# Adapter_board.net
KiCad netlist of a schematic drawn in EAGLE
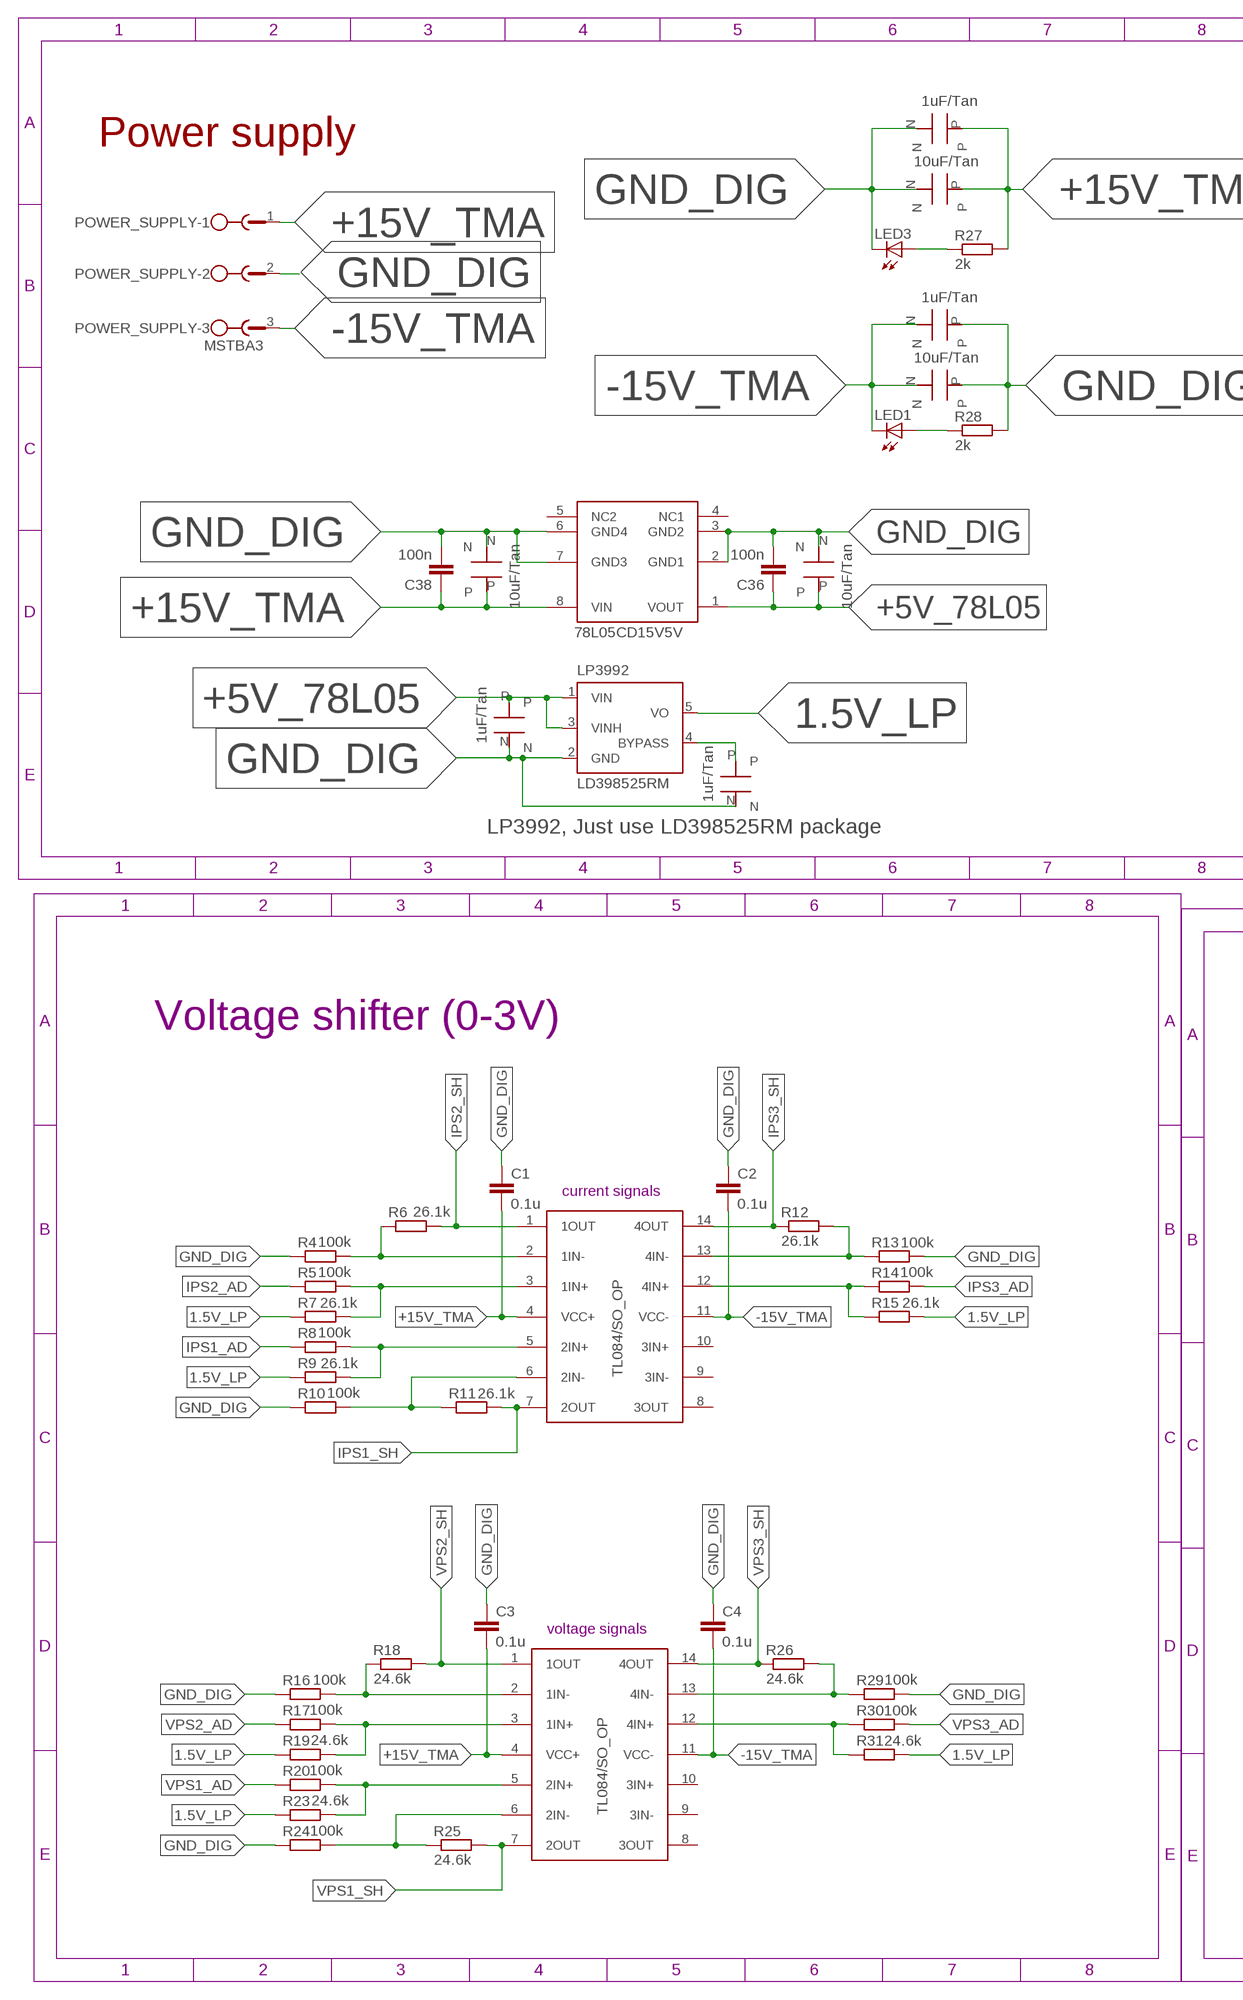
[diagram p0: schematic, sheet 1, part 1 of 2]
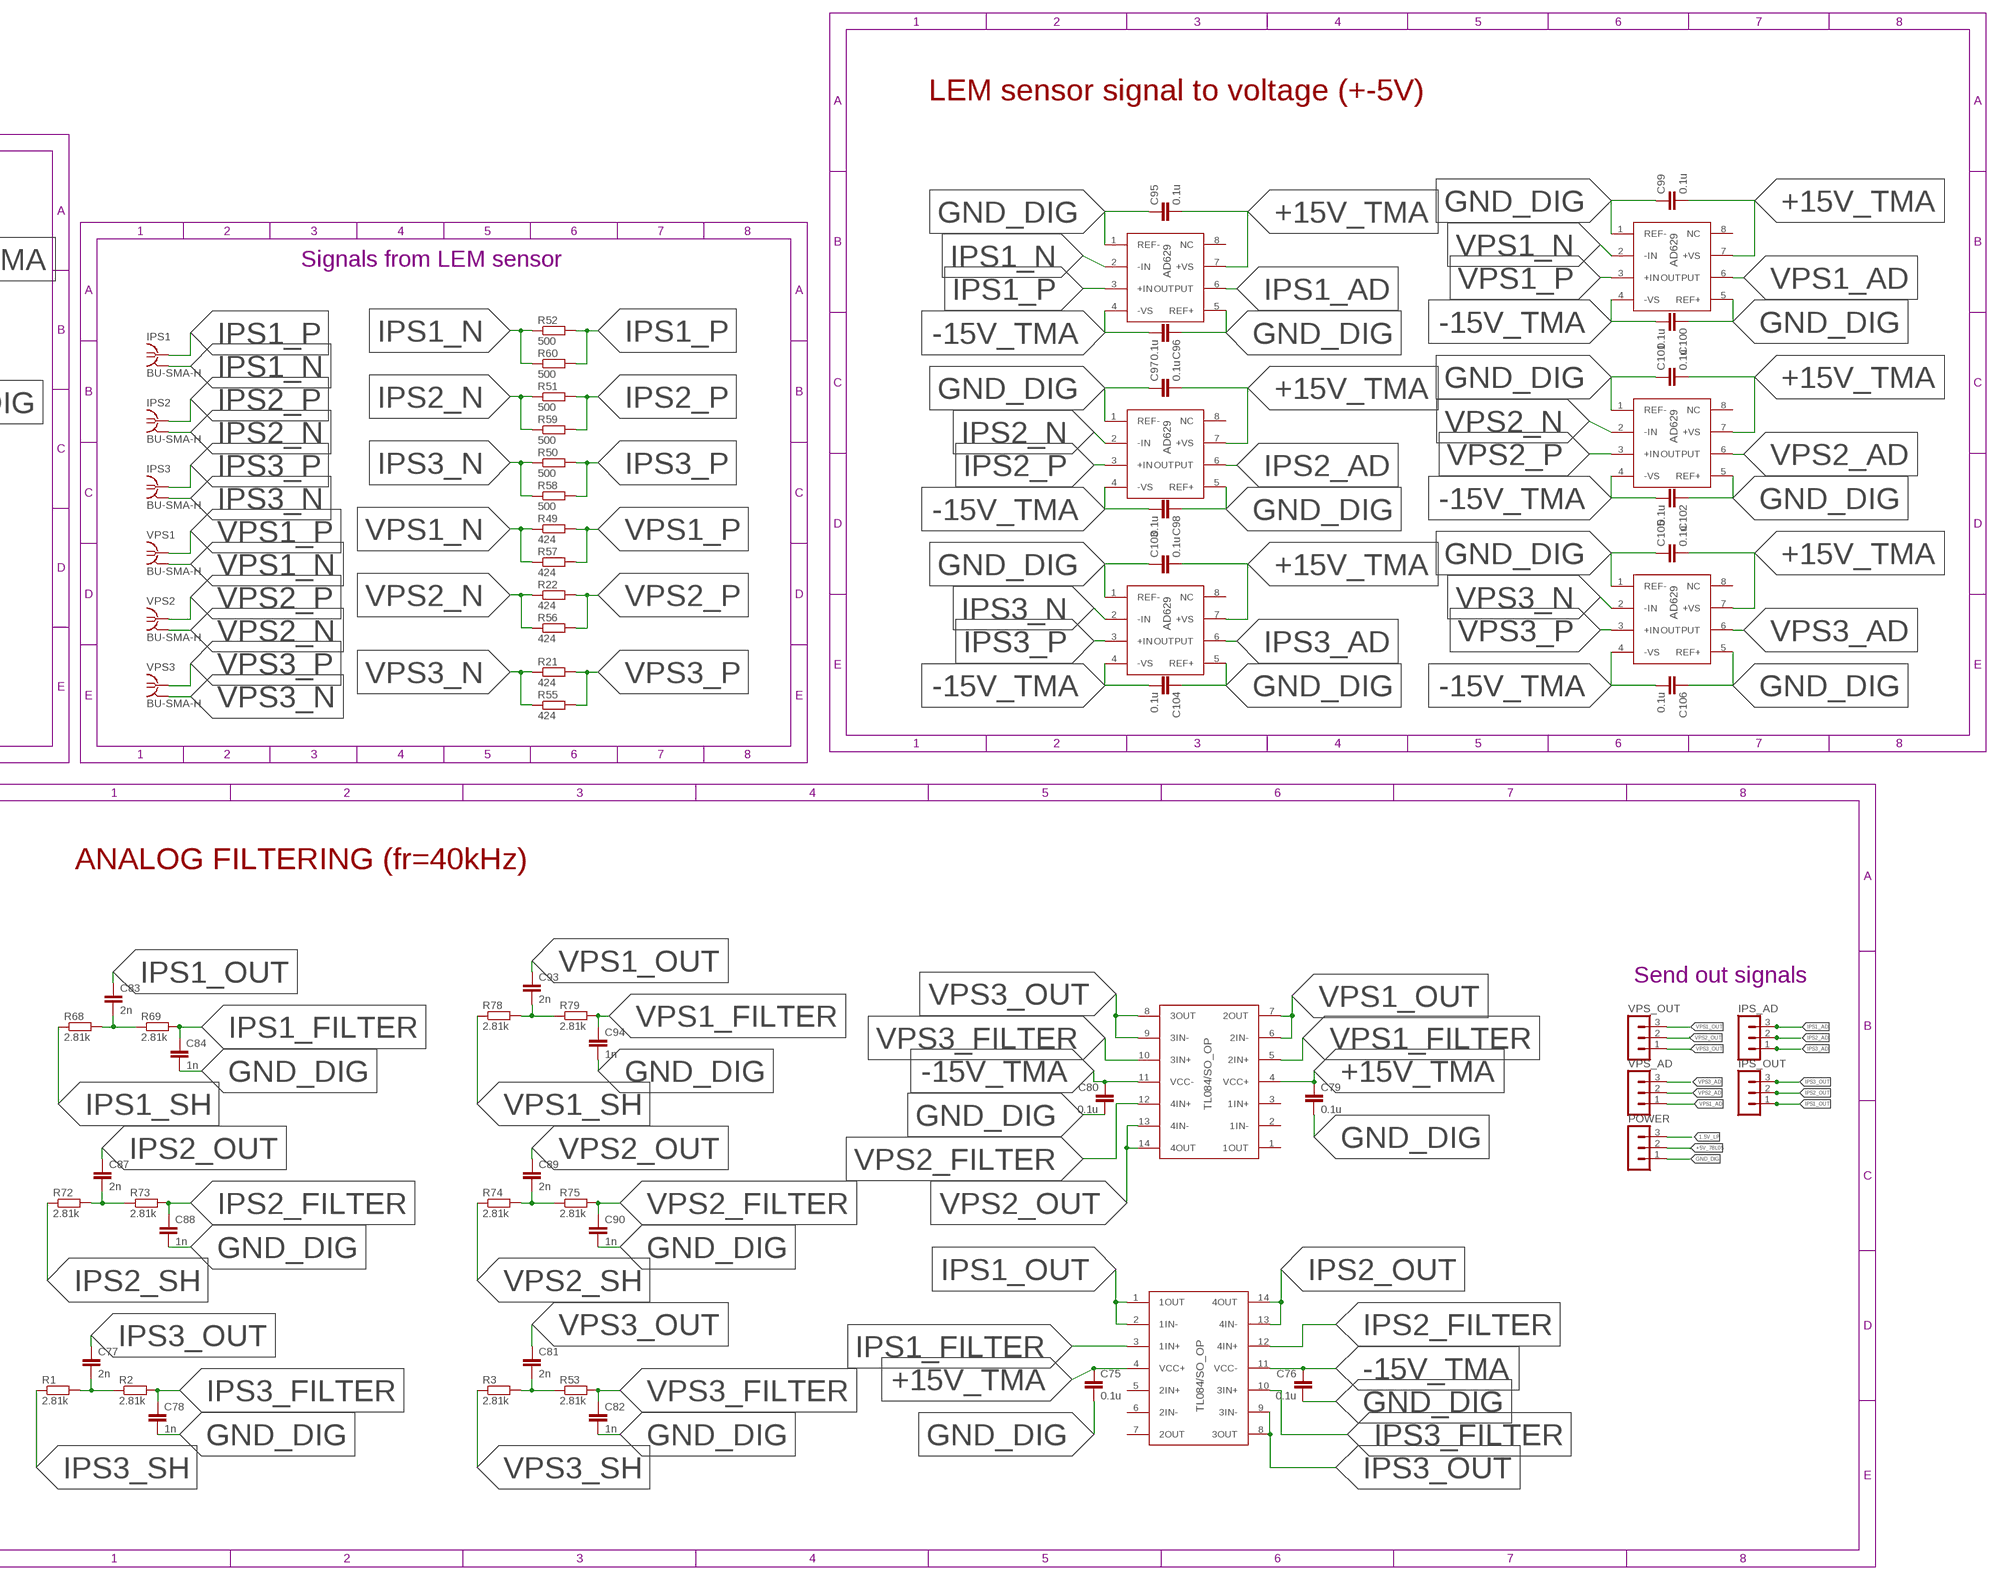
[diagram p1: schematic, sheet 1, part 2 of 2]

(export (version "E")
  (design (tool "Eeschema 10.0.6"))
  (components
    (comp (ref "78L05")
      (value "78L05CD15V5VONLINE")
      (footprint "eagle-import:78L05CD15V5V_LIB")
      (libsource (lib "eagle-import") (part "78L05CD15V5VONLINE"))
    )
    (comp (ref "C1")
      (value "0.1u")
      (footprint "eagle-import:C0805")
      (libsource (lib "eagle-import") (part "C-EUC0805"))
    )
    (comp (ref "C2")
      (value "0.1u")
      (footprint "eagle-import:C0805")
      (libsource (lib "eagle-import") (part "C-EUC0805"))
    )
    (comp (ref "C3")
      (value "0.1u")
      (footprint "eagle-import:C0805")
      (libsource (lib "eagle-import") (part "C-EUC0805"))
    )
    (comp (ref "C4")
      (value "0.1u")
      (footprint "eagle-import:C0805")
      (libsource (lib "eagle-import") (part "C-EUC0805"))
    )
    (comp (ref "C36")
      (value "100n")
      (footprint "eagle-import:C0805")
      (libsource (lib "eagle-import") (part "C-EUC0805"))
    )
    (comp (ref "C37")
      (value "TANTALUM_C_10UF_KEM")
      (footprint "eagle-import:TANTALUM_C_10UF_KEM")
      (libsource (lib "eagle-import") (part "TANTALUM_C_10UF_KEM"))
    )
    (comp (ref "C38")
      (value "100n")
      (footprint "eagle-import:C0805")
      (libsource (lib "eagle-import") (part "C-EUC0805"))
    )
    (comp (ref "C75")
      (value "0.1u")
      (footprint "eagle-import:C0805")
      (libsource (lib "eagle-import") (part "C-EUC0805"))
    )
    (comp (ref "C76")
      (value "0.1u")
      (footprint "eagle-import:C0805")
      (libsource (lib "eagle-import") (part "C-EUC0805"))
    )
    (comp (ref "C77")
      (value "2n")
      (footprint "eagle-import:C0805")
      (libsource (lib "eagle-import") (part "C-EUC0805"))
    )
    (comp (ref "C78")
      (value "1n")
      (footprint "eagle-import:C0805")
      (libsource (lib "eagle-import") (part "C-EUC0805"))
    )
    (comp (ref "C79")
      (value "0.1u")
      (footprint "eagle-import:C0805")
      (libsource (lib "eagle-import") (part "C-EUC0805"))
    )
    (comp (ref "C80")
      (value "0.1u")
      (footprint "eagle-import:C0805")
      (libsource (lib "eagle-import") (part "C-EUC0805"))
    )
    (comp (ref "C81")
      (value "2n")
      (footprint "eagle-import:C0805")
      (libsource (lib "eagle-import") (part "C-EUC0805"))
    )
    (comp (ref "C82")
      (value "1n")
      (footprint "eagle-import:C0805")
      (libsource (lib "eagle-import") (part "C-EUC0805"))
    )
    (comp (ref "C83")
      (value "2n")
      (footprint "eagle-import:C0805")
      (libsource (lib "eagle-import") (part "C-EUC0805"))
    )
    (comp (ref "C84")
      (value "1n")
      (footprint "eagle-import:C0805")
      (libsource (lib "eagle-import") (part "C-EUC0805"))
    )
    (comp (ref "C87")
      (value "2n")
      (footprint "eagle-import:C0805")
      (libsource (lib "eagle-import") (part "C-EUC0805"))
    )
    (comp (ref "C88")
      (value "1n")
      (footprint "eagle-import:C0805")
      (libsource (lib "eagle-import") (part "C-EUC0805"))
    )
    (comp (ref "C89")
      (value "2n")
      (footprint "eagle-import:C0805")
      (libsource (lib "eagle-import") (part "C-EUC0805"))
    )
    (comp (ref "C90")
      (value "1n")
      (footprint "eagle-import:C0805")
      (libsource (lib "eagle-import") (part "C-EUC0805"))
    )
    (comp (ref "C93")
      (value "2n")
      (footprint "eagle-import:C0805")
      (libsource (lib "eagle-import") (part "C-EUC0805"))
    )
    (comp (ref "C94")
      (value "1n")
      (footprint "eagle-import:C0805")
      (libsource (lib "eagle-import") (part "C-EUC0805"))
    )
    (comp (ref "C95")
      (value "0.1u")
      (footprint "eagle-import:C0805")
      (libsource (lib "eagle-import") (part "C-EUC0805"))
    )
    (comp (ref "C96")
      (value "0.1u")
      (footprint "eagle-import:C0805")
      (libsource (lib "eagle-import") (part "C-EUC0805"))
    )
    (comp (ref "C97")
      (value "0.1u")
      (footprint "eagle-import:C0805")
      (libsource (lib "eagle-import") (part "C-EUC0805"))
    )
    (comp (ref "C98")
      (value "0.1u")
      (footprint "eagle-import:C0805")
      (libsource (lib "eagle-import") (part "C-EUC0805"))
    )
    (comp (ref "C99")
      (value "0.1u")
      (footprint "eagle-import:C0805")
      (libsource (lib "eagle-import") (part "C-EUC0805"))
    )
    (comp (ref "C100")
      (value "0.1u")
      (footprint "eagle-import:C0805")
      (libsource (lib "eagle-import") (part "C-EUC0805"))
    )
    (comp (ref "C101")
      (value "0.1u")
      (footprint "eagle-import:C0805")
      (libsource (lib "eagle-import") (part "C-EUC0805"))
    )
    (comp (ref "C102")
      (value "0.1u")
      (footprint "eagle-import:C0805")
      (libsource (lib "eagle-import") (part "C-EUC0805"))
    )
    (comp (ref "C103")
      (value "0.1u")
      (footprint "eagle-import:C0805")
      (libsource (lib "eagle-import") (part "C-EUC0805"))
    )
    (comp (ref "C104")
      (value "0.1u")
      (footprint "eagle-import:C0805")
      (libsource (lib "eagle-import") (part "C-EUC0805"))
    )
    (comp (ref "C105")
      (value "0.1u")
      (footprint "eagle-import:C0805")
      (libsource (lib "eagle-import") (part "C-EUC0805"))
    )
    (comp (ref "C106")
      (value "0.1u")
      (footprint "eagle-import:C0805")
      (libsource (lib "eagle-import") (part "C-EUC0805"))
    )
    (comp (ref "IPS1")
      (value "BU-SMA-H")
      (footprint "eagle-import:BU-SMA-H")
      (libsource (lib "eagle-import") (part "BU-SMA-H"))
    )
    (comp (ref "IPS2")
      (value "BU-SMA-H")
      (footprint "eagle-import:BU-SMA-H")
      (libsource (lib "eagle-import") (part "BU-SMA-H"))
    )
    (comp (ref "IPS3")
      (value "BU-SMA-H")
      (footprint "eagle-import:BU-SMA-H")
      (libsource (lib "eagle-import") (part "BU-SMA-H"))
    )
    (comp (ref "IPS_AD")
      (value "MA03-1")
      (footprint "eagle-import:MA03-1")
      (libsource (lib "eagle-import") (part "MA03-1"))
    )
    (comp (ref "IPS_OUT")
      (value "MA03-1")
      (footprint "eagle-import:MA03-1")
      (libsource (lib "eagle-import") (part "MA03-1"))
    )
    (comp (ref "LED1")
      (value "LEDCHIPLED_0805")
      (footprint "eagle-import:CHIPLED_0805")
      (libsource (lib "eagle-import") (part "LEDCHIPLED_0805"))
    )
    (comp (ref "LED3")
      (value "LEDCHIPLED_0805")
      (footprint "eagle-import:CHIPLED_0805")
      (libsource (lib "eagle-import") (part "LEDCHIPLED_0805"))
    )
    (comp (ref "LP3992")
      (value "LD398525RM")
      (footprint "eagle-import:SOT23-5L")
      (libsource (lib "eagle-import") (part "LD3985M25R"))
    )
    (comp (ref "POWER")
      (value "MA03-1")
      (footprint "eagle-import:MA03-1")
      (libsource (lib "eagle-import") (part "MA03-1"))
    )
    (comp (ref "POWER_SUPPLY")
      (value "MSTBA3")
      (footprint "eagle-import:MSTBA3")
      (fields (field (name "MF") "FARNELL") (field (name "MPN") "1757255"))
      (libsource (lib "eagle-import") (part "MSTBA3"))
    )
    (comp (ref "R1")
      (value "2.81k")
      (footprint "eagle-import:R0805")
      (libsource (lib "eagle-import") (part "R-EU_R0805"))
    )
    (comp (ref "R2")
      (value "2.81k")
      (footprint "eagle-import:R0805")
      (libsource (lib "eagle-import") (part "R-EU_R0805"))
    )
    (comp (ref "R3")
      (value "2.81k")
      (footprint "eagle-import:R0805")
      (libsource (lib "eagle-import") (part "R-EU_R0805"))
    )
    (comp (ref "R4")
      (value "100k")
      (footprint "eagle-import:R0805")
      (libsource (lib "eagle-import") (part "R-EU_R0805"))
    )
    (comp (ref "R5")
      (value "100k")
      (footprint "eagle-import:R0805")
      (libsource (lib "eagle-import") (part "R-EU_R0805"))
    )
    (comp (ref "R6")
      (value "26.1k")
      (footprint "eagle-import:R0805")
      (libsource (lib "eagle-import") (part "R-EU_R0805"))
    )
    (comp (ref "R7")
      (value "26.1k")
      (footprint "eagle-import:R0805")
      (libsource (lib "eagle-import") (part "R-EU_R0805"))
    )
    (comp (ref "R8")
      (value "100k")
      (footprint "eagle-import:R0805")
      (libsource (lib "eagle-import") (part "R-EU_R0805"))
    )
    (comp (ref "R9")
      (value "26.1k")
      (footprint "eagle-import:R0805")
      (libsource (lib "eagle-import") (part "R-EU_R0805"))
    )
    (comp (ref "R10")
      (value "100k")
      (footprint "eagle-import:R0805")
      (libsource (lib "eagle-import") (part "R-EU_R0805"))
    )
    (comp (ref "R11")
      (value "26.1k")
      (footprint "eagle-import:R0805")
      (libsource (lib "eagle-import") (part "R-EU_R0805"))
    )
    (comp (ref "R12")
      (value "26.1k")
      (footprint "eagle-import:R0805")
      (libsource (lib "eagle-import") (part "R-EU_R0805"))
    )
    (comp (ref "R13")
      (value "100k")
      (footprint "eagle-import:R0805")
      (libsource (lib "eagle-import") (part "R-EU_R0805"))
    )
    (comp (ref "R14")
      (value "100k")
      (footprint "eagle-import:R0805")
      (libsource (lib "eagle-import") (part "R-EU_R0805"))
    )
    (comp (ref "R15")
      (value "26.1k")
      (footprint "eagle-import:R0805")
      (libsource (lib "eagle-import") (part "R-EU_R0805"))
    )
    (comp (ref "R16")
      (value "100k")
      (footprint "eagle-import:R0805")
      (libsource (lib "eagle-import") (part "R-EU_R0805"))
    )
    (comp (ref "R17")
      (value "100k")
      (footprint "eagle-import:R0805")
      (libsource (lib "eagle-import") (part "R-EU_R0805"))
    )
    (comp (ref "R18")
      (value "24.6k")
      (footprint "eagle-import:R0805")
      (libsource (lib "eagle-import") (part "R-EU_R0805"))
    )
    (comp (ref "R19")
      (value "24.6k")
      (footprint "eagle-import:R0805")
      (libsource (lib "eagle-import") (part "R-EU_R0805"))
    )
    (comp (ref "R20")
      (value "100k")
      (footprint "eagle-import:R0805")
      (libsource (lib "eagle-import") (part "R-EU_R0805"))
    )
    (comp (ref "R21")
      (value "424")
      (footprint "eagle-import:R1206")
      (libsource (lib "eagle-import") (part "R-EU_R1206"))
    )
    (comp (ref "R22")
      (value "424")
      (footprint "eagle-import:R1206")
      (libsource (lib "eagle-import") (part "R-EU_R1206"))
    )
    (comp (ref "R23")
      (value "24.6k")
      (footprint "eagle-import:R0805")
      (libsource (lib "eagle-import") (part "R-EU_R0805"))
    )
    (comp (ref "R24")
      (value "100k")
      (footprint "eagle-import:R0805")
      (libsource (lib "eagle-import") (part "R-EU_R0805"))
    )
    (comp (ref "R25")
      (value "24.6k")
      (footprint "eagle-import:R0805")
      (libsource (lib "eagle-import") (part "R-EU_R0805"))
    )
    (comp (ref "R26")
      (value "24.6k")
      (footprint "eagle-import:R0805")
      (libsource (lib "eagle-import") (part "R-EU_R0805"))
    )
    (comp (ref "R27")
      (value "2k")
      (footprint "eagle-import:R0805")
      (libsource (lib "eagle-import") (part "R-EU_R0805"))
    )
    (comp (ref "R28")
      (value "2k")
      (footprint "eagle-import:R0805")
      (libsource (lib "eagle-import") (part "R-EU_R0805"))
    )
    (comp (ref "R29")
      (value "100k")
      (footprint "eagle-import:R0805")
      (libsource (lib "eagle-import") (part "R-EU_R0805"))
    )
    (comp (ref "R30")
      (value "100k")
      (footprint "eagle-import:R0805")
      (libsource (lib "eagle-import") (part "R-EU_R0805"))
    )
    (comp (ref "R31")
      (value "24.6k")
      (footprint "eagle-import:R0805")
      (libsource (lib "eagle-import") (part "R-EU_R0805"))
    )
    (comp (ref "R49")
      (value "424")
      (footprint "eagle-import:R1206")
      (libsource (lib "eagle-import") (part "R-EU_R1206"))
    )
    (comp (ref "R50")
      (value "500")
      (footprint "eagle-import:R1206")
      (libsource (lib "eagle-import") (part "R-EU_R1206"))
    )
    (comp (ref "R51")
      (value "500")
      (footprint "eagle-import:R1206")
      (libsource (lib "eagle-import") (part "R-EU_R1206"))
    )
    (comp (ref "R52")
      (value "500")
      (footprint "eagle-import:R1206")
      (libsource (lib "eagle-import") (part "R-EU_R1206"))
    )
    (comp (ref "R53")
      (value "2.81k")
      (footprint "eagle-import:R0805")
      (libsource (lib "eagle-import") (part "R-EU_R0805"))
    )
    (comp (ref "R55")
      (value "424")
      (footprint "eagle-import:R1206")
      (libsource (lib "eagle-import") (part "R-EU_R1206"))
    )
    (comp (ref "R56")
      (value "424")
      (footprint "eagle-import:R1206")
      (libsource (lib "eagle-import") (part "R-EU_R1206"))
    )
    (comp (ref "R57")
      (value "424")
      (footprint "eagle-import:R1206")
      (libsource (lib "eagle-import") (part "R-EU_R1206"))
    )
    (comp (ref "R58")
      (value "500")
      (footprint "eagle-import:R1206")
      (libsource (lib "eagle-import") (part "R-EU_R1206"))
    )
    (comp (ref "R59")
      (value "500")
      (footprint "eagle-import:R1206")
      (libsource (lib "eagle-import") (part "R-EU_R1206"))
    )
    (comp (ref "R60")
      (value "500")
      (footprint "eagle-import:R1206")
      (libsource (lib "eagle-import") (part "R-EU_R1206"))
    )
    (comp (ref "R68")
      (value "2.81k")
      (footprint "eagle-import:R0805")
      (libsource (lib "eagle-import") (part "R-EU_R0805"))
    )
    (comp (ref "R69")
      (value "2.81k")
      (footprint "eagle-import:R0805")
      (libsource (lib "eagle-import") (part "R-EU_R0805"))
    )
    (comp (ref "R72")
      (value "2.81k")
      (footprint "eagle-import:R0805")
      (libsource (lib "eagle-import") (part "R-EU_R0805"))
    )
    (comp (ref "R73")
      (value "2.81k")
      (footprint "eagle-import:R0805")
      (libsource (lib "eagle-import") (part "R-EU_R0805"))
    )
    (comp (ref "R74")
      (value "2.81k")
      (footprint "eagle-import:R0805")
      (libsource (lib "eagle-import") (part "R-EU_R0805"))
    )
    (comp (ref "R75")
      (value "2.81k")
      (footprint "eagle-import:R0805")
      (libsource (lib "eagle-import") (part "R-EU_R0805"))
    )
    (comp (ref "R78")
      (value "2.81k")
      (footprint "eagle-import:R0805")
      (libsource (lib "eagle-import") (part "R-EU_R0805"))
    )
    (comp (ref "R79")
      (value "2.81k")
      (footprint "eagle-import:R0805")
      (libsource (lib "eagle-import") (part "R-EU_R0805"))
    )
    (comp (ref "U$1")
      (value "TL084/SO_OPONLINE")
      (footprint "eagle-import:TL084_SO_OP_LIB")
      (libsource (lib "eagle-import") (part "TL084/SO_OPONLINE"))
    )
    (comp (ref "U$2")
      (value "TL084/SO_OPONLINE")
      (footprint "eagle-import:TL084_SO_OP_LIB")
      (libsource (lib "eagle-import") (part "TL084/SO_OPONLINE"))
    )
    (comp (ref "U$3")
      (value "TANTALUM_C_1UF_KEMTANTALUM_C_1UF_KEM")
      (footprint "eagle-import:TANTALUM_C_1UF_KEM")
      (libsource (lib "eagle-import") (part "TANTALUM_C_1UF_KEMTANTALUM_C_1UF_KEM"))
    )
    (comp (ref "U$4")
      (value "TL084/SO_OPONLINE")
      (footprint "eagle-import:TL084_SO_OP_LIB")
      (libsource (lib "eagle-import") (part "TL084/SO_OPONLINE"))
    )
    (comp (ref "U$5")
      (value "TANTALUM_C_1UF_KEMTANTALUM_C_1UF_KEM")
      (footprint "eagle-import:TANTALUM_C_1UF_KEM")
      (libsource (lib "eagle-import") (part "TANTALUM_C_1UF_KEMTANTALUM_C_1UF_KEM"))
    )
    (comp (ref "U$6")
      (value "TL084/SO_OPONLINE")
      (footprint "eagle-import:TL084_SO_OP_LIB")
      (libsource (lib "eagle-import") (part "TL084/SO_OPONLINE"))
    )
    (comp (ref "U$10")
      (value "TANTALUM_C_1UF_KEMTANTALUM_C_1UF_KEM")
      (footprint "eagle-import:TANTALUM_C_1UF_KEM")
      (libsource (lib "eagle-import") (part "TANTALUM_C_1UF_KEMTANTALUM_C_1UF_KEM"))
    )
    (comp (ref "U$11")
      (value "TANTALUM_C_10UF_KEM")
      (footprint "eagle-import:TANTALUM_C_10UF_KEM")
      (libsource (lib "eagle-import") (part "TANTALUM_C_10UF_KEM"))
    )
    (comp (ref "U$12")
      (value "TANTALUM_C_1UF_KEMTANTALUM_C_1UF_KEM")
      (footprint "eagle-import:TANTALUM_C_1UF_KEM")
      (libsource (lib "eagle-import") (part "TANTALUM_C_1UF_KEMTANTALUM_C_1UF_KEM"))
    )
    (comp (ref "U$14")
      (value "TANTALUM_C_10UF_KEM")
      (footprint "eagle-import:TANTALUM_C_10UF_KEM")
      (libsource (lib "eagle-import") (part "TANTALUM_C_10UF_KEM"))
    )
    (comp (ref "U$24")
      (value "AD629_DIFFAONLINE")
      (footprint "eagle-import:AD629_DIFFA_LIB")
      (libsource (lib "eagle-import") (part "AD629_DIFFAONLINE"))
    )
    (comp (ref "U$27")
      (value "AD629_DIFFAONLINE")
      (footprint "eagle-import:AD629_DIFFA_LIB")
      (libsource (lib "eagle-import") (part "AD629_DIFFAONLINE"))
    )
    (comp (ref "U$28")
      (value "AD629_DIFFAONLINE")
      (footprint "eagle-import:AD629_DIFFA_LIB")
      (libsource (lib "eagle-import") (part "AD629_DIFFAONLINE"))
    )
    (comp (ref "U$29")
      (value "AD629_DIFFAONLINE")
      (footprint "eagle-import:AD629_DIFFA_LIB")
      (libsource (lib "eagle-import") (part "AD629_DIFFAONLINE"))
    )
    (comp (ref "U$30")
      (value "AD629_DIFFAONLINE")
      (footprint "eagle-import:AD629_DIFFA_LIB")
      (libsource (lib "eagle-import") (part "AD629_DIFFAONLINE"))
    )
    (comp (ref "U$31")
      (value "AD629_DIFFAONLINE")
      (footprint "eagle-import:AD629_DIFFA_LIB")
      (libsource (lib "eagle-import") (part "AD629_DIFFAONLINE"))
    )
    (comp (ref "U$66")
      (value "TANTALUM_C_10UF_KEM")
      (footprint "eagle-import:TANTALUM_C_10UF_KEM")
      (libsource (lib "eagle-import") (part "TANTALUM_C_10UF_KEM"))
    )
    (comp (ref "VPS1")
      (value "BU-SMA-H")
      (footprint "eagle-import:BU-SMA-H")
      (libsource (lib "eagle-import") (part "BU-SMA-H"))
    )
    (comp (ref "VPS2")
      (value "BU-SMA-H")
      (footprint "eagle-import:BU-SMA-H")
      (libsource (lib "eagle-import") (part "BU-SMA-H"))
    )
    (comp (ref "VPS3")
      (value "BU-SMA-H")
      (footprint "eagle-import:BU-SMA-H")
      (libsource (lib "eagle-import") (part "BU-SMA-H"))
    )
    (comp (ref "VPS_AD")
      (value "MA03-1")
      (footprint "eagle-import:MA03-1")
      (libsource (lib "eagle-import") (part "MA03-1"))
    )
    (comp (ref "VPS_OUT")
      (value "MA03-1")
      (footprint "eagle-import:MA03-1")
      (libsource (lib "eagle-import") (part "MA03-1"))
    )
  )
  (nets
    (net (code "1") (name "+5V_78L05") (class "Default")
      (node (ref "78L05") (pin "1") (pinfunction "VOUT_1") (pintype "bidirectional"))
      (node (ref "C36") (pin "1") (pinfunction "1_1") (pintype "passive"))
      (node (ref "C37") (pin "P") (pinfunction "P_P") (pintype "bidirectional"))
      (node (ref "LP3992") (pin "1") (pinfunction "VIN_1") (pintype "input"))
      (node (ref "LP3992") (pin "3") (pinfunction "VINH_3") (pintype "input"))
      (node (ref "POWER") (pin "2") (pinfunction "2_2") (pintype "passive"))
      (node (ref "U$3") (pin "P") (pinfunction "P_P") (pintype "bidirectional"))
    )
    (net (code "2") (name "+15V_TMA") (class "Default")
      (node (ref "78L05") (pin "8") (pinfunction "VIN_8") (pintype "bidirectional"))
      (node (ref "C1") (pin "2") (pinfunction "2_2") (pintype "passive"))
      (node (ref "C101") (pin "2") (pinfunction "2_2") (pintype "passive"))
      (node (ref "C103") (pin "2") (pinfunction "2_2") (pintype "passive"))
      (node (ref "C105") (pin "2") (pinfunction "2_2") (pintype "passive"))
      (node (ref "C3") (pin "2") (pinfunction "2_2") (pintype "passive"))
      (node (ref "C38") (pin "1") (pinfunction "1_1") (pintype "passive"))
      (node (ref "C75") (pin "1") (pinfunction "1_1") (pintype "passive"))
      (node (ref "C79") (pin "1") (pinfunction "1_1") (pintype "passive"))
      (node (ref "C95") (pin "2") (pinfunction "2_2") (pintype "passive"))
      (node (ref "C97") (pin "2") (pinfunction "2_2") (pintype "passive"))
      (node (ref "C99") (pin "2") (pinfunction "2_2") (pintype "passive"))
      (node (ref "POWER_SUPPLY") (pin "1") (pinfunction "1_1") (pintype "passive"))
      (node (ref "R27") (pin "2") (pinfunction "2_2") (pintype "passive"))
      (node (ref "U$1") (pin "4") (pinfunction "VCC+_4") (pintype "bidirectional"))
      (node (ref "U$10") (pin "P") (pinfunction "P_P") (pintype "bidirectional"))
      (node (ref "U$11") (pin "P") (pinfunction "P_P") (pintype "bidirectional"))
      (node (ref "U$2") (pin "4") (pinfunction "VCC+_4") (pintype "bidirectional"))
      (node (ref "U$24") (pin "7") (pinfunction "+VS_7") (pintype "bidirectional"))
      (node (ref "U$27") (pin "7") (pinfunction "+VS_7") (pintype "bidirectional"))
      (node (ref "U$28") (pin "7") (pinfunction "+VS_7") (pintype "bidirectional"))
      (node (ref "U$29") (pin "7") (pinfunction "+VS_7") (pintype "bidirectional"))
      (node (ref "U$30") (pin "7") (pinfunction "+VS_7") (pintype "bidirectional"))
      (node (ref "U$31") (pin "7") (pinfunction "+VS_7") (pintype "bidirectional"))
      (node (ref "U$4") (pin "4") (pinfunction "VCC+_4") (pintype "bidirectional"))
      (node (ref "U$6") (pin "4") (pinfunction "VCC+_4") (pintype "bidirectional"))
      (node (ref "U$66") (pin "P") (pinfunction "P_P") (pintype "bidirectional"))
    )
    (net (code "3") (name "-15V_TMA") (class "Default")
      (node (ref "C100") (pin "2") (pinfunction "2_2") (pintype "passive"))
      (node (ref "C102") (pin "2") (pinfunction "2_2") (pintype "passive"))
      (node (ref "C104") (pin "2") (pinfunction "2_2") (pintype "passive"))
      (node (ref "C106") (pin "2") (pinfunction "2_2") (pintype "passive"))
      (node (ref "C2") (pin "2") (pinfunction "2_2") (pintype "passive"))
      (node (ref "C4") (pin "2") (pinfunction "2_2") (pintype "passive"))
      (node (ref "C76") (pin "1") (pinfunction "1_1") (pintype "passive"))
      (node (ref "C80") (pin "1") (pinfunction "1_1") (pintype "passive"))
      (node (ref "C96") (pin "2") (pinfunction "2_2") (pintype "passive"))
      (node (ref "C98") (pin "2") (pinfunction "2_2") (pintype "passive"))
      (node (ref "LED1") (pin "C") (pinfunction "C_C") (pintype "passive"))
      (node (ref "POWER_SUPPLY") (pin "3") (pinfunction "1_3") (pintype "passive"))
      (node (ref "U$1") (pin "11") (pinfunction "VCC-_11") (pintype "bidirectional"))
      (node (ref "U$12") (pin "N") (pinfunction "N_N") (pintype "bidirectional"))
      (node (ref "U$14") (pin "N") (pinfunction "N_N") (pintype "bidirectional"))
      (node (ref "U$2") (pin "11") (pinfunction "VCC-_11") (pintype "bidirectional"))
      (node (ref "U$24") (pin "4") (pinfunction "-VS_4") (pintype "bidirectional"))
      (node (ref "U$27") (pin "4") (pinfunction "-VS_4") (pintype "bidirectional"))
      (node (ref "U$28") (pin "4") (pinfunction "-VS_4") (pintype "bidirectional"))
      (node (ref "U$29") (pin "4") (pinfunction "-VS_4") (pintype "bidirectional"))
      (node (ref "U$30") (pin "4") (pinfunction "-VS_4") (pintype "bidirectional"))
      (node (ref "U$31") (pin "4") (pinfunction "-VS_4") (pintype "bidirectional"))
      (node (ref "U$4") (pin "11") (pinfunction "VCC-_11") (pintype "bidirectional"))
      (node (ref "U$6") (pin "11") (pinfunction "VCC-_11") (pintype "bidirectional"))
    )
    (net (code "4") (name "1.5V_LP") (class "Default")
      (node (ref "LP3992") (pin "5") (pinfunction "VO_5") (pintype "output"))
      (node (ref "POWER") (pin "3") (pinfunction "3_3") (pintype "passive"))
      (node (ref "R15") (pin "2") (pinfunction "2_2") (pintype "passive"))
      (node (ref "R19") (pin "1") (pinfunction "1_1") (pintype "passive"))
      (node (ref "R23") (pin "1") (pinfunction "1_1") (pintype "passive"))
      (node (ref "R31") (pin "2") (pinfunction "2_2") (pintype "passive"))
      (node (ref "R7") (pin "1") (pinfunction "1_1") (pintype "passive"))
      (node (ref "R9") (pin "1") (pinfunction "1_1") (pintype "passive"))
    )
    (net (code "5") (name "GND_DIG") (class "Default")
      (node (ref "78L05") (pin "2") (pinfunction "GND1_2") (pintype "bidirectional"))
      (node (ref "78L05") (pin "3") (pinfunction "GND2_3") (pintype "bidirectional"))
      (node (ref "78L05") (pin "6") (pinfunction "GND4_6") (pintype "bidirectional"))
      (node (ref "78L05") (pin "7") (pinfunction "GND3_7") (pintype "bidirectional"))
      (node (ref "C1") (pin "1") (pinfunction "1_1") (pintype "passive"))
      (node (ref "C100") (pin "1") (pinfunction "1_1") (pintype "passive"))
      (node (ref "C101") (pin "1") (pinfunction "1_1") (pintype "passive"))
      (node (ref "C102") (pin "1") (pinfunction "1_1") (pintype "passive"))
      (node (ref "C103") (pin "1") (pinfunction "1_1") (pintype "passive"))
      (node (ref "C104") (pin "1") (pinfunction "1_1") (pintype "passive"))
      (node (ref "C105") (pin "1") (pinfunction "1_1") (pintype "passive"))
      (node (ref "C106") (pin "1") (pinfunction "1_1") (pintype "passive"))
      (node (ref "C2") (pin "1") (pinfunction "1_1") (pintype "passive"))
      (node (ref "C3") (pin "1") (pinfunction "1_1") (pintype "passive"))
      (node (ref "C36") (pin "2") (pinfunction "2_2") (pintype "passive"))
      (node (ref "C37") (pin "N") (pinfunction "N_N") (pintype "bidirectional"))
      (node (ref "C38") (pin "2") (pinfunction "2_2") (pintype "passive"))
      (node (ref "C4") (pin "1") (pinfunction "1_1") (pintype "passive"))
      (node (ref "C75") (pin "2") (pinfunction "2_2") (pintype "passive"))
      (node (ref "C76") (pin "2") (pinfunction "2_2") (pintype "passive"))
      (node (ref "C78") (pin "2") (pinfunction "2_2") (pintype "passive"))
      (node (ref "C79") (pin "2") (pinfunction "2_2") (pintype "passive"))
      (node (ref "C80") (pin "2") (pinfunction "2_2") (pintype "passive"))
      (node (ref "C82") (pin "2") (pinfunction "2_2") (pintype "passive"))
      (node (ref "C84") (pin "2") (pinfunction "2_2") (pintype "passive"))
      (node (ref "C88") (pin "2") (pinfunction "2_2") (pintype "passive"))
      (node (ref "C90") (pin "2") (pinfunction "2_2") (pintype "passive"))
      (node (ref "C94") (pin "2") (pinfunction "2_2") (pintype "passive"))
      (node (ref "C95") (pin "1") (pinfunction "1_1") (pintype "passive"))
      (node (ref "C96") (pin "1") (pinfunction "1_1") (pintype "passive"))
      (node (ref "C97") (pin "1") (pinfunction "1_1") (pintype "passive"))
      (node (ref "C98") (pin "1") (pinfunction "1_1") (pintype "passive"))
      (node (ref "C99") (pin "1") (pinfunction "1_1") (pintype "passive"))
      (node (ref "LED3") (pin "C") (pinfunction "C_C") (pintype "passive"))
      (node (ref "LP3992") (pin "2") (pinfunction "GND_2") (pintype "power_in"))
      (node (ref "POWER") (pin "1") (pinfunction "1_1") (pintype "passive"))
      (node (ref "POWER_SUPPLY") (pin "2") (pinfunction "1_2") (pintype "passive"))
      (node (ref "R10") (pin "1") (pinfunction "1_1") (pintype "passive"))
      (node (ref "R13") (pin "2") (pinfunction "2_2") (pintype "passive"))
      (node (ref "R16") (pin "1") (pinfunction "1_1") (pintype "passive"))
      (node (ref "R24") (pin "1") (pinfunction "1_1") (pintype "passive"))
      (node (ref "R28") (pin "2") (pinfunction "2_2") (pintype "passive"))
      (node (ref "R29") (pin "2") (pinfunction "2_2") (pintype "passive"))
      (node (ref "R4") (pin "1") (pinfunction "1_1") (pintype "passive"))
      (node (ref "U$10") (pin "N") (pinfunction "N_N") (pintype "bidirectional"))
      (node (ref "U$11") (pin "N") (pinfunction "N_N") (pintype "bidirectional"))
      (node (ref "U$12") (pin "P") (pinfunction "P_P") (pintype "bidirectional"))
      (node (ref "U$14") (pin "P") (pinfunction "P_P") (pintype "bidirectional"))
      (node (ref "U$24") (pin "1") (pinfunction "REF-_1") (pintype "bidirectional"))
      (node (ref "U$24") (pin "5") (pinfunction "REF+_5") (pintype "bidirectional"))
      (node (ref "U$27") (pin "1") (pinfunction "REF-_1") (pintype "bidirectional"))
      (node (ref "U$27") (pin "5") (pinfunction "REF+_5") (pintype "bidirectional"))
      (node (ref "U$28") (pin "1") (pinfunction "REF-_1") (pintype "bidirectional"))
      (node (ref "U$28") (pin "5") (pinfunction "REF+_5") (pintype "bidirectional"))
      (node (ref "U$29") (pin "1") (pinfunction "REF-_1") (pintype "bidirectional"))
      (node (ref "U$29") (pin "5") (pinfunction "REF+_5") (pintype "bidirectional"))
      (node (ref "U$3") (pin "N") (pinfunction "N_N") (pintype "bidirectional"))
      (node (ref "U$30") (pin "1") (pinfunction "REF-_1") (pintype "bidirectional"))
      (node (ref "U$30") (pin "5") (pinfunction "REF+_5") (pintype "bidirectional"))
      (node (ref "U$31") (pin "1") (pinfunction "REF-_1") (pintype "bidirectional"))
      (node (ref "U$31") (pin "5") (pinfunction "REF+_5") (pintype "bidirectional"))
      (node (ref "U$5") (pin "N") (pinfunction "N_N") (pintype "bidirectional"))
      (node (ref "U$66") (pin "N") (pinfunction "N_N") (pintype "bidirectional"))
    )
    (net (code "6") (name "IPS1_AD") (class "Default")
      (node (ref "IPS_AD") (pin "3") (pinfunction "3_3") (pintype "passive"))
      (node (ref "R8") (pin "1") (pinfunction "1_1") (pintype "passive"))
      (node (ref "U$24") (pin "6") (pinfunction "OUTPUT_6") (pintype "bidirectional"))
    )
    (net (code "7") (name "IPS1_FILTER") (class "Default")
      (node (ref "C84") (pin "1") (pinfunction "1_1") (pintype "passive"))
      (node (ref "R69") (pin "2") (pinfunction "2_2") (pintype "passive"))
      (node (ref "U$4") (pin "3") (pinfunction "1IN+_3") (pintype "bidirectional"))
    )
    (net (code "8") (name "IPS1_N") (class "Default")
      (node (ref "IPS1") (pin "2") (pinfunction "2_2") (pintype "passive"))
      (node (ref "IPS1") (pin "3") (pinfunction "2_3") (pintype "passive"))
      (node (ref "IPS1") (pin "4") (pinfunction "2_4") (pintype "passive"))
      (node (ref "IPS1") (pin "5") (pinfunction "2_5") (pintype "passive"))
      (node (ref "R52") (pin "1") (pinfunction "1_1") (pintype "passive"))
      (node (ref "R60") (pin "1") (pinfunction "1_1") (pintype "passive"))
      (node (ref "U$24") (pin "2") (pinfunction "-IN_2") (pintype "bidirectional"))
    )
    (net (code "9") (name "IPS1_OUT") (class "Default")
      (node (ref "C83") (pin "1") (pinfunction "1_1") (pintype "passive"))
      (node (ref "IPS_OUT") (pin "1") (pinfunction "1_1") (pintype "passive"))
      (node (ref "U$4") (pin "1") (pinfunction "1OUT_1") (pintype "bidirectional"))
      (node (ref "U$4") (pin "2") (pinfunction "1IN-_2") (pintype "bidirectional"))
    )
    (net (code "10") (name "IPS1_P") (class "Default")
      (node (ref "IPS1") (pin "1") (pinfunction "1_1") (pintype "passive"))
      (node (ref "R52") (pin "2") (pinfunction "2_2") (pintype "passive"))
      (node (ref "R60") (pin "2") (pinfunction "2_2") (pintype "passive"))
      (node (ref "U$24") (pin "3") (pinfunction "+IN_3") (pintype "bidirectional"))
    )
    (net (code "11") (name "IPS1_SH") (class "Default")
      (node (ref "R11") (pin "2") (pinfunction "2_2") (pintype "passive"))
      (node (ref "R68") (pin "1") (pinfunction "1_1") (pintype "passive"))
      (node (ref "U$1") (pin "7") (pinfunction "2OUT_7") (pintype "bidirectional"))
    )
    (net (code "12") (name "IPS2_AD") (class "Default")
      (node (ref "IPS_AD") (pin "2") (pinfunction "2_2") (pintype "passive"))
      (node (ref "R5") (pin "1") (pinfunction "1_1") (pintype "passive"))
      (node (ref "U$27") (pin "6") (pinfunction "OUTPUT_6") (pintype "bidirectional"))
    )
    (net (code "13") (name "IPS2_FILTER") (class "Default")
      (node (ref "C88") (pin "1") (pinfunction "1_1") (pintype "passive"))
      (node (ref "R73") (pin "2") (pinfunction "2_2") (pintype "passive"))
      (node (ref "U$4") (pin "12") (pinfunction "4IN+_12") (pintype "bidirectional"))
    )
    (net (code "14") (name "IPS2_N") (class "Default")
      (node (ref "IPS2") (pin "2") (pinfunction "2_2") (pintype "passive"))
      (node (ref "IPS2") (pin "3") (pinfunction "2_3") (pintype "passive"))
      (node (ref "IPS2") (pin "4") (pinfunction "2_4") (pintype "passive"))
      (node (ref "IPS2") (pin "5") (pinfunction "2_5") (pintype "passive"))
      (node (ref "R51") (pin "1") (pinfunction "1_1") (pintype "passive"))
      (node (ref "R59") (pin "1") (pinfunction "1_1") (pintype "passive"))
      (node (ref "U$27") (pin "2") (pinfunction "-IN_2") (pintype "bidirectional"))
    )
    (net (code "15") (name "IPS2_OUT") (class "Default")
      (node (ref "C87") (pin "1") (pinfunction "1_1") (pintype "passive"))
      (node (ref "IPS_OUT") (pin "2") (pinfunction "2_2") (pintype "passive"))
      (node (ref "U$4") (pin "13") (pinfunction "4IN-_13") (pintype "bidirectional"))
      (node (ref "U$4") (pin "14") (pinfunction "4OUT_14") (pintype "bidirectional"))
    )
    (net (code "16") (name "IPS2_P") (class "Default")
      (node (ref "IPS2") (pin "1") (pinfunction "1_1") (pintype "passive"))
      (node (ref "R51") (pin "2") (pinfunction "2_2") (pintype "passive"))
      (node (ref "R59") (pin "2") (pinfunction "2_2") (pintype "passive"))
      (node (ref "U$27") (pin "3") (pinfunction "+IN_3") (pintype "bidirectional"))
    )
    (net (code "17") (name "IPS2_SH") (class "Default")
      (node (ref "R6") (pin "2") (pinfunction "2_2") (pintype "passive"))
      (node (ref "R72") (pin "1") (pinfunction "1_1") (pintype "passive"))
      (node (ref "U$1") (pin "1") (pinfunction "1OUT_1") (pintype "bidirectional"))
    )
    (net (code "18") (name "IPS3_AD") (class "Default")
      (node (ref "IPS_AD") (pin "1") (pinfunction "1_1") (pintype "passive"))
      (node (ref "R14") (pin "2") (pinfunction "2_2") (pintype "passive"))
      (node (ref "U$30") (pin "6") (pinfunction "OUTPUT_6") (pintype "bidirectional"))
    )
    (net (code "19") (name "IPS3_FILTER") (class "Default")
      (node (ref "C78") (pin "1") (pinfunction "1_1") (pintype "passive"))
      (node (ref "R2") (pin "2") (pinfunction "2_2") (pintype "passive"))
      (node (ref "U$4") (pin "10") (pinfunction "3IN+_10") (pintype "bidirectional"))
    )
    (net (code "20") (name "IPS3_N") (class "Default")
      (node (ref "IPS3") (pin "2") (pinfunction "2_2") (pintype "passive"))
      (node (ref "IPS3") (pin "3") (pinfunction "2_3") (pintype "passive"))
      (node (ref "IPS3") (pin "4") (pinfunction "2_4") (pintype "passive"))
      (node (ref "IPS3") (pin "5") (pinfunction "2_5") (pintype "passive"))
      (node (ref "R50") (pin "1") (pinfunction "1_1") (pintype "passive"))
      (node (ref "R58") (pin "1") (pinfunction "1_1") (pintype "passive"))
      (node (ref "U$30") (pin "2") (pinfunction "-IN_2") (pintype "bidirectional"))
    )
    (net (code "21") (name "IPS3_OUT") (class "Default")
      (node (ref "C77") (pin "1") (pinfunction "1_1") (pintype "passive"))
      (node (ref "IPS_OUT") (pin "3") (pinfunction "3_3") (pintype "passive"))
      (node (ref "U$4") (pin "8") (pinfunction "3OUT_8") (pintype "bidirectional"))
      (node (ref "U$4") (pin "9") (pinfunction "3IN-_9") (pintype "bidirectional"))
    )
    (net (code "22") (name "IPS3_P") (class "Default")
      (node (ref "IPS3") (pin "1") (pinfunction "1_1") (pintype "passive"))
      (node (ref "R50") (pin "2") (pinfunction "2_2") (pintype "passive"))
      (node (ref "R58") (pin "2") (pinfunction "2_2") (pintype "passive"))
      (node (ref "U$30") (pin "3") (pinfunction "+IN_3") (pintype "bidirectional"))
    )
    (net (code "23") (name "IPS3_SH") (class "Default")
      (node (ref "R1") (pin "1") (pinfunction "1_1") (pintype "passive"))
      (node (ref "R12") (pin "1") (pinfunction "1_1") (pintype "passive"))
      (node (ref "U$1") (pin "14") (pinfunction "4OUT_14") (pintype "bidirectional"))
    )
    (net (code "24") (name "Net-(C77-Pad2)") (class "Default")
      (node (ref "C77") (pin "2") (pinfunction "2_2") (pintype "passive"))
      (node (ref "R1") (pin "2") (pinfunction "2_2") (pintype "passive"))
      (node (ref "R2") (pin "1") (pinfunction "1_1") (pintype "passive"))
    )
    (net (code "25") (name "Net-(C81-Pad2)") (class "Default")
      (node (ref "C81") (pin "2") (pinfunction "2_2") (pintype "passive"))
      (node (ref "R3") (pin "2") (pinfunction "2_2") (pintype "passive"))
      (node (ref "R53") (pin "1") (pinfunction "1_1") (pintype "passive"))
    )
    (net (code "26") (name "Net-(C83-Pad2)") (class "Default")
      (node (ref "C83") (pin "2") (pinfunction "2_2") (pintype "passive"))
      (node (ref "R68") (pin "2") (pinfunction "2_2") (pintype "passive"))
      (node (ref "R69") (pin "1") (pinfunction "1_1") (pintype "passive"))
    )
    (net (code "27") (name "Net-(C87-Pad2)") (class "Default")
      (node (ref "C87") (pin "2") (pinfunction "2_2") (pintype "passive"))
      (node (ref "R72") (pin "2") (pinfunction "2_2") (pintype "passive"))
      (node (ref "R73") (pin "1") (pinfunction "1_1") (pintype "passive"))
    )
    (net (code "28") (name "Net-(C89-Pad2)") (class "Default")
      (node (ref "C89") (pin "2") (pinfunction "2_2") (pintype "passive"))
      (node (ref "R74") (pin "2") (pinfunction "2_2") (pintype "passive"))
      (node (ref "R75") (pin "1") (pinfunction "1_1") (pintype "passive"))
    )
    (net (code "29") (name "Net-(C93-Pad2)") (class "Default")
      (node (ref "C93") (pin "2") (pinfunction "2_2") (pintype "passive"))
      (node (ref "R78") (pin "2") (pinfunction "2_2") (pintype "passive"))
      (node (ref "R79") (pin "1") (pinfunction "1_1") (pintype "passive"))
    )
    (net (code "30") (name "Net-(LED1-PadA)") (class "Default")
      (node (ref "LED1") (pin "A") (pinfunction "A_A") (pintype "passive"))
      (node (ref "R28") (pin "1") (pinfunction "1_1") (pintype "passive"))
    )
    (net (code "31") (name "Net-(LED3-PadA)") (class "Default")
      (node (ref "LED3") (pin "A") (pinfunction "A_A") (pintype "passive"))
      (node (ref "R27") (pin "1") (pinfunction "1_1") (pintype "passive"))
    )
    (net (code "32") (name "Net-(LP3992-BYPASS)") (class "Default")
      (node (ref "LP3992") (pin "4") (pinfunction "BYPASS_4") (pintype "passive"))
      (node (ref "U$5") (pin "P") (pinfunction "P_P") (pintype "bidirectional"))
    )
    (net (code "33") (name "Net-(U$1-1IN+)") (class "Default")
      (node (ref "R5") (pin "2") (pinfunction "2_2") (pintype "passive"))
      (node (ref "R7") (pin "2") (pinfunction "2_2") (pintype "passive"))
      (node (ref "U$1") (pin "3") (pinfunction "1IN+_3") (pintype "bidirectional"))
    )
    (net (code "34") (name "Net-(U$1-1IN-)") (class "Default")
      (node (ref "R4") (pin "2") (pinfunction "2_2") (pintype "passive"))
      (node (ref "R6") (pin "1") (pinfunction "1_1") (pintype "passive"))
      (node (ref "U$1") (pin "2") (pinfunction "1IN-_2") (pintype "bidirectional"))
    )
    (net (code "35") (name "Net-(U$1-2IN+)") (class "Default")
      (node (ref "R8") (pin "2") (pinfunction "2_2") (pintype "passive"))
      (node (ref "R9") (pin "2") (pinfunction "2_2") (pintype "passive"))
      (node (ref "U$1") (pin "5") (pinfunction "2IN+_5") (pintype "bidirectional"))
    )
    (net (code "36") (name "Net-(U$1-2IN-)") (class "Default")
      (node (ref "R10") (pin "2") (pinfunction "2_2") (pintype "passive"))
      (node (ref "R11") (pin "1") (pinfunction "1_1") (pintype "passive"))
      (node (ref "U$1") (pin "6") (pinfunction "2IN-_6") (pintype "bidirectional"))
    )
    (net (code "37") (name "Net-(U$1-4IN+)") (class "Default")
      (node (ref "R14") (pin "1") (pinfunction "1_1") (pintype "passive"))
      (node (ref "R15") (pin "1") (pinfunction "1_1") (pintype "passive"))
      (node (ref "U$1") (pin "12") (pinfunction "4IN+_12") (pintype "bidirectional"))
    )
    (net (code "38") (name "Net-(U$1-4IN-)") (class "Default")
      (node (ref "R12") (pin "2") (pinfunction "2_2") (pintype "passive"))
      (node (ref "R13") (pin "1") (pinfunction "1_1") (pintype "passive"))
      (node (ref "U$1") (pin "13") (pinfunction "4IN-_13") (pintype "bidirectional"))
    )
    (net (code "39") (name "Net-(U$2-1IN+)") (class "Default")
      (node (ref "R17") (pin "2") (pinfunction "2_2") (pintype "passive"))
      (node (ref "R19") (pin "2") (pinfunction "2_2") (pintype "passive"))
      (node (ref "U$2") (pin "3") (pinfunction "1IN+_3") (pintype "bidirectional"))
    )
    (net (code "40") (name "Net-(U$2-1IN-)") (class "Default")
      (node (ref "R16") (pin "2") (pinfunction "2_2") (pintype "passive"))
      (node (ref "R18") (pin "1") (pinfunction "1_1") (pintype "passive"))
      (node (ref "U$2") (pin "2") (pinfunction "1IN-_2") (pintype "bidirectional"))
    )
    (net (code "41") (name "Net-(U$2-2IN+)") (class "Default")
      (node (ref "R20") (pin "2") (pinfunction "2_2") (pintype "passive"))
      (node (ref "R23") (pin "2") (pinfunction "2_2") (pintype "passive"))
      (node (ref "U$2") (pin "5") (pinfunction "2IN+_5") (pintype "bidirectional"))
    )
    (net (code "42") (name "Net-(U$2-2IN-)") (class "Default")
      (node (ref "R24") (pin "2") (pinfunction "2_2") (pintype "passive"))
      (node (ref "R25") (pin "1") (pinfunction "1_1") (pintype "passive"))
      (node (ref "U$2") (pin "6") (pinfunction "2IN-_6") (pintype "bidirectional"))
    )
    (net (code "43") (name "Net-(U$2-4IN+)") (class "Default")
      (node (ref "R30") (pin "1") (pinfunction "1_1") (pintype "passive"))
      (node (ref "R31") (pin "1") (pinfunction "1_1") (pintype "passive"))
      (node (ref "U$2") (pin "12") (pinfunction "4IN+_12") (pintype "bidirectional"))
    )
    (net (code "44") (name "Net-(U$2-4IN-)") (class "Default")
      (node (ref "R26") (pin "2") (pinfunction "2_2") (pintype "passive"))
      (node (ref "R29") (pin "1") (pinfunction "1_1") (pintype "passive"))
      (node (ref "U$2") (pin "13") (pinfunction "4IN-_13") (pintype "bidirectional"))
    )
    (net (code "45") (name "VPS1_AD") (class "Default")
      (node (ref "R20") (pin "1") (pinfunction "1_1") (pintype "passive"))
      (node (ref "U$28") (pin "6") (pinfunction "OUTPUT_6") (pintype "bidirectional"))
      (node (ref "VPS_AD") (pin "1") (pinfunction "1_1") (pintype "passive"))
    )
    (net (code "46") (name "VPS1_FILTER") (class "Default")
      (node (ref "C94") (pin "1") (pinfunction "1_1") (pintype "passive"))
      (node (ref "R79") (pin "2") (pinfunction "2_2") (pintype "passive"))
      (node (ref "U$6") (pin "5") (pinfunction "2IN+_5") (pintype "bidirectional"))
    )
    (net (code "47") (name "VPS1_N") (class "Default")
      (node (ref "R49") (pin "1") (pinfunction "1_1") (pintype "passive"))
      (node (ref "R57") (pin "1") (pinfunction "1_1") (pintype "passive"))
      (node (ref "U$28") (pin "2") (pinfunction "-IN_2") (pintype "bidirectional"))
      (node (ref "VPS1") (pin "2") (pinfunction "2_2") (pintype "passive"))
      (node (ref "VPS1") (pin "3") (pinfunction "2_3") (pintype "passive"))
      (node (ref "VPS1") (pin "4") (pinfunction "2_4") (pintype "passive"))
      (node (ref "VPS1") (pin "5") (pinfunction "2_5") (pintype "passive"))
    )
    (net (code "48") (name "VPS1_OUT") (class "Default")
      (node (ref "C93") (pin "1") (pinfunction "1_1") (pintype "passive"))
      (node (ref "U$6") (pin "6") (pinfunction "2IN-_6") (pintype "bidirectional"))
      (node (ref "U$6") (pin "7") (pinfunction "2OUT_7") (pintype "bidirectional"))
      (node (ref "VPS_OUT") (pin "3") (pinfunction "3_3") (pintype "passive"))
    )
    (net (code "49") (name "VPS1_P") (class "Default")
      (node (ref "R49") (pin "2") (pinfunction "2_2") (pintype "passive"))
      (node (ref "R57") (pin "2") (pinfunction "2_2") (pintype "passive"))
      (node (ref "U$28") (pin "3") (pinfunction "+IN_3") (pintype "bidirectional"))
      (node (ref "VPS1") (pin "1") (pinfunction "1_1") (pintype "passive"))
    )
    (net (code "50") (name "VPS1_SH") (class "Default")
      (node (ref "R25") (pin "2") (pinfunction "2_2") (pintype "passive"))
      (node (ref "R78") (pin "1") (pinfunction "1_1") (pintype "passive"))
      (node (ref "U$2") (pin "7") (pinfunction "2OUT_7") (pintype "bidirectional"))
    )
    (net (code "51") (name "VPS2_AD") (class "Default")
      (node (ref "R17") (pin "1") (pinfunction "1_1") (pintype "passive"))
      (node (ref "U$29") (pin "6") (pinfunction "OUTPUT_6") (pintype "bidirectional"))
      (node (ref "VPS_AD") (pin "2") (pinfunction "2_2") (pintype "passive"))
    )
    (net (code "52") (name "VPS2_FILTER") (class "Default")
      (node (ref "C90") (pin "1") (pinfunction "1_1") (pintype "passive"))
      (node (ref "R75") (pin "2") (pinfunction "2_2") (pintype "passive"))
      (node (ref "U$6") (pin "12") (pinfunction "4IN+_12") (pintype "bidirectional"))
    )
    (net (code "53") (name "VPS2_N") (class "Default")
      (node (ref "R22") (pin "1") (pinfunction "1_1") (pintype "passive"))
      (node (ref "R56") (pin "1") (pinfunction "1_1") (pintype "passive"))
      (node (ref "U$29") (pin "2") (pinfunction "-IN_2") (pintype "bidirectional"))
      (node (ref "VPS2") (pin "2") (pinfunction "2_2") (pintype "passive"))
      (node (ref "VPS2") (pin "3") (pinfunction "2_3") (pintype "passive"))
      (node (ref "VPS2") (pin "4") (pinfunction "2_4") (pintype "passive"))
      (node (ref "VPS2") (pin "5") (pinfunction "2_5") (pintype "passive"))
    )
    (net (code "54") (name "VPS2_OUT") (class "Default")
      (node (ref "C89") (pin "1") (pinfunction "1_1") (pintype "passive"))
      (node (ref "U$6") (pin "13") (pinfunction "4IN-_13") (pintype "bidirectional"))
      (node (ref "U$6") (pin "14") (pinfunction "4OUT_14") (pintype "bidirectional"))
      (node (ref "VPS_OUT") (pin "2") (pinfunction "2_2") (pintype "passive"))
    )
    (net (code "55") (name "VPS2_P") (class "Default")
      (node (ref "R22") (pin "2") (pinfunction "2_2") (pintype "passive"))
      (node (ref "R56") (pin "2") (pinfunction "2_2") (pintype "passive"))
      (node (ref "U$29") (pin "3") (pinfunction "+IN_3") (pintype "bidirectional"))
      (node (ref "VPS2") (pin "1") (pinfunction "1_1") (pintype "passive"))
    )
    (net (code "56") (name "VPS2_SH") (class "Default")
      (node (ref "R18") (pin "2") (pinfunction "2_2") (pintype "passive"))
      (node (ref "R74") (pin "1") (pinfunction "1_1") (pintype "passive"))
      (node (ref "U$2") (pin "1") (pinfunction "1OUT_1") (pintype "bidirectional"))
    )
    (net (code "57") (name "VPS3_AD") (class "Default")
      (node (ref "R30") (pin "2") (pinfunction "2_2") (pintype "passive"))
      (node (ref "U$31") (pin "6") (pinfunction "OUTPUT_6") (pintype "bidirectional"))
      (node (ref "VPS_AD") (pin "3") (pinfunction "3_3") (pintype "passive"))
    )
    (net (code "58") (name "VPS3_FILTER") (class "Default")
      (node (ref "C82") (pin "1") (pinfunction "1_1") (pintype "passive"))
      (node (ref "R53") (pin "2") (pinfunction "2_2") (pintype "passive"))
      (node (ref "U$6") (pin "10") (pinfunction "3IN+_10") (pintype "bidirectional"))
    )
    (net (code "59") (name "VPS3_N") (class "Default")
      (node (ref "R21") (pin "1") (pinfunction "1_1") (pintype "passive"))
      (node (ref "R55") (pin "1") (pinfunction "1_1") (pintype "passive"))
      (node (ref "U$31") (pin "2") (pinfunction "-IN_2") (pintype "bidirectional"))
      (node (ref "VPS3") (pin "2") (pinfunction "2_2") (pintype "passive"))
      (node (ref "VPS3") (pin "3") (pinfunction "2_3") (pintype "passive"))
      (node (ref "VPS3") (pin "4") (pinfunction "2_4") (pintype "passive"))
      (node (ref "VPS3") (pin "5") (pinfunction "2_5") (pintype "passive"))
    )
    (net (code "60") (name "VPS3_OUT") (class "Default")
      (node (ref "C81") (pin "1") (pinfunction "1_1") (pintype "passive"))
      (node (ref "U$6") (pin "8") (pinfunction "3OUT_8") (pintype "bidirectional"))
      (node (ref "U$6") (pin "9") (pinfunction "3IN-_9") (pintype "bidirectional"))
      (node (ref "VPS_OUT") (pin "1") (pinfunction "1_1") (pintype "passive"))
    )
    (net (code "61") (name "VPS3_P") (class "Default")
      (node (ref "R21") (pin "2") (pinfunction "2_2") (pintype "passive"))
      (node (ref "R55") (pin "2") (pinfunction "2_2") (pintype "passive"))
      (node (ref "U$31") (pin "3") (pinfunction "+IN_3") (pintype "bidirectional"))
      (node (ref "VPS3") (pin "1") (pinfunction "1_1") (pintype "passive"))
    )
    (net (code "62") (name "VPS3_SH") (class "Default")
      (node (ref "R26") (pin "1") (pinfunction "1_1") (pintype "passive"))
      (node (ref "R3") (pin "1") (pinfunction "1_1") (pintype "passive"))
      (node (ref "U$2") (pin "14") (pinfunction "4OUT_14") (pintype "bidirectional"))
    )
    (net (code "63") (name "unconnected-(78L05-NC1-Pad4)") (class "Default")
      (node (ref "78L05") (pin "4") (pinfunction "NC1_4") (pintype "bidirectional"))
    )
    (net (code "64") (name "unconnected-(78L05-NC2-Pad5)") (class "Default")
      (node (ref "78L05") (pin "5") (pinfunction "NC2_5") (pintype "bidirectional"))
    )
    (net (code "65") (name "unconnected-(U$1-3IN+-Pad10)") (class "Default")
      (node (ref "U$1") (pin "10") (pinfunction "3IN+_10") (pintype "bidirectional"))
    )
    (net (code "66") (name "unconnected-(U$1-3IN--Pad9)") (class "Default")
      (node (ref "U$1") (pin "9") (pinfunction "3IN-_9") (pintype "bidirectional"))
    )
    (net (code "67") (name "unconnected-(U$1-3OUT-Pad8)") (class "Default")
      (node (ref "U$1") (pin "8") (pinfunction "3OUT_8") (pintype "bidirectional"))
    )
    (net (code "68") (name "unconnected-(U$2-3IN+-Pad10)") (class "Default")
      (node (ref "U$2") (pin "10") (pinfunction "3IN+_10") (pintype "bidirectional"))
    )
    (net (code "69") (name "unconnected-(U$2-3IN--Pad9)") (class "Default")
      (node (ref "U$2") (pin "9") (pinfunction "3IN-_9") (pintype "bidirectional"))
    )
    (net (code "70") (name "unconnected-(U$2-3OUT-Pad8)") (class "Default")
      (node (ref "U$2") (pin "8") (pinfunction "3OUT_8") (pintype "bidirectional"))
    )
    (net (code "71") (name "unconnected-(U$4-2IN+-Pad5)") (class "Default")
      (node (ref "U$4") (pin "5") (pinfunction "2IN+_5") (pintype "bidirectional"))
    )
    (net (code "72") (name "unconnected-(U$4-2IN--Pad6)") (class "Default")
      (node (ref "U$4") (pin "6") (pinfunction "2IN-_6") (pintype "bidirectional"))
    )
    (net (code "73") (name "unconnected-(U$4-2OUT-Pad7)") (class "Default")
      (node (ref "U$4") (pin "7") (pinfunction "2OUT_7") (pintype "bidirectional"))
    )
    (net (code "74") (name "unconnected-(U$6-1IN+-Pad3)") (class "Default")
      (node (ref "U$6") (pin "3") (pinfunction "1IN+_3") (pintype "bidirectional"))
    )
    (net (code "75") (name "unconnected-(U$6-1IN--Pad2)") (class "Default")
      (node (ref "U$6") (pin "2") (pinfunction "1IN-_2") (pintype "bidirectional"))
    )
    (net (code "76") (name "unconnected-(U$6-1OUT-Pad1)") (class "Default")
      (node (ref "U$6") (pin "1") (pinfunction "1OUT_1") (pintype "bidirectional"))
    )
    (net (code "77") (name "unconnected-(U$24-NC-Pad8)") (class "Default")
      (node (ref "U$24") (pin "8") (pinfunction "NC_8") (pintype "bidirectional"))
    )
    (net (code "78") (name "unconnected-(U$27-NC-Pad8)") (class "Default")
      (node (ref "U$27") (pin "8") (pinfunction "NC_8") (pintype "bidirectional"))
    )
    (net (code "79") (name "unconnected-(U$28-NC-Pad8)") (class "Default")
      (node (ref "U$28") (pin "8") (pinfunction "NC_8") (pintype "bidirectional"))
    )
    (net (code "80") (name "unconnected-(U$29-NC-Pad8)") (class "Default")
      (node (ref "U$29") (pin "8") (pinfunction "NC_8") (pintype "bidirectional"))
    )
    (net (code "81") (name "unconnected-(U$30-NC-Pad8)") (class "Default")
      (node (ref "U$30") (pin "8") (pinfunction "NC_8") (pintype "bidirectional"))
    )
    (net (code "82") (name "unconnected-(U$31-NC-Pad8)") (class "Default")
      (node (ref "U$31") (pin "8") (pinfunction "NC_8") (pintype "bidirectional"))
    )
  )
)
